# ESPREMOTE.net
KiCad netlist of a schematic drawn in EAGLE
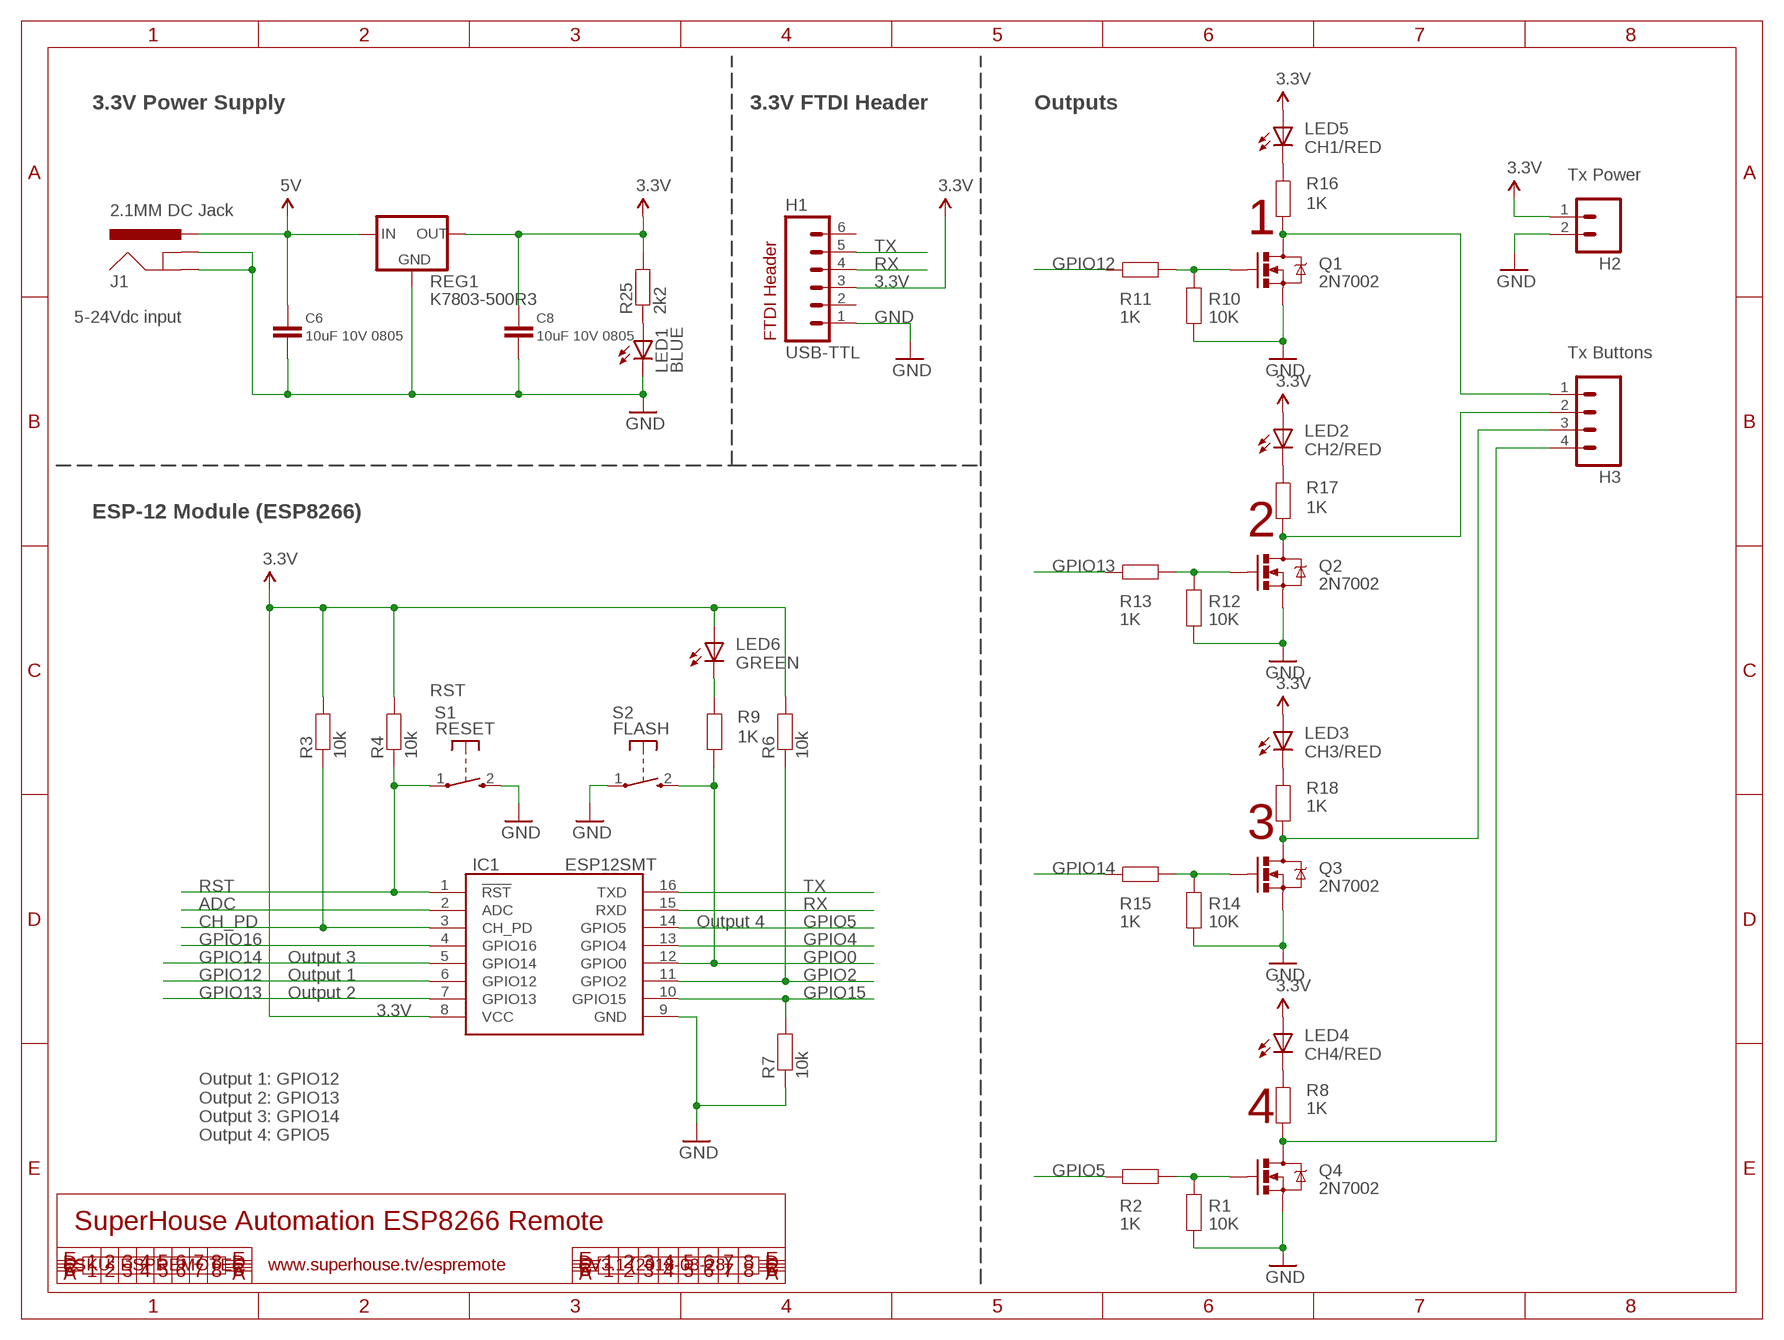
[diagram p0: schematic, sheet 1]

(export (version "E")
  (design (tool "Eeschema 10.0.6"))
  (components
    (comp (ref "C6")
      (value "10uF 10V 0805")
      (footprint "eagle-import:C0805")
      (libsource (lib "eagle-import") (part "C-EUC0805"))
    )
    (comp (ref "C8")
      (value "10uF 10V 0805")
      (footprint "eagle-import:C0805")
      (libsource (lib "eagle-import") (part "C-EUC0805"))
    )
    (comp (ref "H1")
      (value "USB-TTL")
      (footprint "eagle-import:1X06")
      (libsource (lib "eagle-import") (part "M06SIP"))
    )
    (comp (ref "H2")
      (value "M02PTH")
      (footprint "eagle-import:1X02")
      (libsource (lib "eagle-import") (part "M02PTH"))
    )
    (comp (ref "H3")
      (value "M04PTH")
      (footprint "eagle-import:1X04")
      (libsource (lib "eagle-import") (part "M04PTH"))
    )
    (comp (ref "IC1")
      (value "ESP12SMT")
      (footprint "eagle-import:ESP12")
      (libsource (lib "eagle-import") (part "ESP12SMT"))
    )
    (comp (ref "J1")
      (value "2.1MM DC Jack")
      (footprint "eagle-import:POWER_JACK_PTH_SLOTS")
      (libsource (lib "eagle-import") (part "POWER_JACKPTH_SLOTS"))
    )
    (comp (ref "LED1")
      (value "BLUE")
      (footprint "eagle-import:LED-0603")
      (libsource (lib "eagle-import") (part "LED0603"))
    )
    (comp (ref "LED2")
      (value "CH2/RED")
      (footprint "eagle-import:LED-0603")
      (libsource (lib "eagle-import") (part "freetronics-master-v1_LED0603"))
    )
    (comp (ref "LED3")
      (value "CH3/RED")
      (footprint "eagle-import:LED-0603")
      (libsource (lib "eagle-import") (part "freetronics-master-v1_LED0603"))
    )
    (comp (ref "LED4")
      (value "CH4/RED")
      (footprint "eagle-import:LED-0603")
      (libsource (lib "eagle-import") (part "freetronics-master-v1_LED0603"))
    )
    (comp (ref "LED5")
      (value "CH1/RED")
      (footprint "eagle-import:LED-0603")
      (libsource (lib "eagle-import") (part "freetronics-master-v1_LED0603"))
    )
    (comp (ref "LED6")
      (value "GREEN")
      (footprint "eagle-import:LED-0603")
      (libsource (lib "eagle-import") (part "freetronics-master-v1_LED0603"))
    )
    (comp (ref "Q1")
      (value "2N7002")
      (footprint "eagle-import:SOT23-3")
      (libsource (lib "eagle-import") (part "MOSFET-NCHANNELSMD"))
    )
    (comp (ref "Q2")
      (value "2N7002")
      (footprint "eagle-import:SOT23-3")
      (libsource (lib "eagle-import") (part "MOSFET-NCHANNELSMD"))
    )
    (comp (ref "Q3")
      (value "2N7002")
      (footprint "eagle-import:SOT23-3")
      (libsource (lib "eagle-import") (part "MOSFET-NCHANNELSMD"))
    )
    (comp (ref "Q4")
      (value "2N7002")
      (footprint "eagle-import:SOT23-3")
      (libsource (lib "eagle-import") (part "MOSFET-NCHANNELSMD"))
    )
    (comp (ref "R1")
      (value "10K")
      (footprint "eagle-import:0603")
      (libsource (lib "eagle-import") (part "freetronics-master-v1_RESISTOR0603"))
    )
    (comp (ref "R2")
      (value "1K")
      (footprint "eagle-import:0603")
      (libsource (lib "eagle-import") (part "freetronics-master-v1_RESISTOR0603"))
    )
    (comp (ref "R3")
      (value "10k")
      (footprint "eagle-import:0603")
      (libsource (lib "eagle-import") (part "RESISTOR0603"))
    )
    (comp (ref "R4")
      (value "10k")
      (footprint "eagle-import:0603")
      (libsource (lib "eagle-import") (part "RESISTOR0603"))
    )
    (comp (ref "R6")
      (value "10k")
      (footprint "eagle-import:0603")
      (libsource (lib "eagle-import") (part "RESISTOR0603"))
    )
    (comp (ref "R7")
      (value "10k")
      (footprint "eagle-import:0603")
      (libsource (lib "eagle-import") (part "RESISTOR0603"))
    )
    (comp (ref "R8")
      (value "1K")
      (footprint "eagle-import:0603")
      (libsource (lib "eagle-import") (part "freetronics-master-v1_RESISTOR0603"))
    )
    (comp (ref "R9")
      (value "1K")
      (footprint "eagle-import:0603")
      (libsource (lib "eagle-import") (part "freetronics-master-v1_RESISTOR0603"))
    )
    (comp (ref "R10")
      (value "10K")
      (footprint "eagle-import:0603")
      (libsource (lib "eagle-import") (part "freetronics-master-v1_RESISTOR0603"))
    )
    (comp (ref "R11")
      (value "1K")
      (footprint "eagle-import:0603")
      (libsource (lib "eagle-import") (part "freetronics-master-v1_RESISTOR0603"))
    )
    (comp (ref "R12")
      (value "10K")
      (footprint "eagle-import:0603")
      (libsource (lib "eagle-import") (part "freetronics-master-v1_RESISTOR0603"))
    )
    (comp (ref "R13")
      (value "1K")
      (footprint "eagle-import:0603")
      (libsource (lib "eagle-import") (part "freetronics-master-v1_RESISTOR0603"))
    )
    (comp (ref "R14")
      (value "10K")
      (footprint "eagle-import:0603")
      (libsource (lib "eagle-import") (part "freetronics-master-v1_RESISTOR0603"))
    )
    (comp (ref "R15")
      (value "1K")
      (footprint "eagle-import:0603")
      (libsource (lib "eagle-import") (part "freetronics-master-v1_RESISTOR0603"))
    )
    (comp (ref "R16")
      (value "1K")
      (footprint "eagle-import:0603")
      (libsource (lib "eagle-import") (part "freetronics-master-v1_RESISTOR0603"))
    )
    (comp (ref "R17")
      (value "1K")
      (footprint "eagle-import:0603")
      (libsource (lib "eagle-import") (part "freetronics-master-v1_RESISTOR0603"))
    )
    (comp (ref "R18")
      (value "1K")
      (footprint "eagle-import:0603")
      (libsource (lib "eagle-import") (part "freetronics-master-v1_RESISTOR0603"))
    )
    (comp (ref "R25")
      (value "2k2")
      (footprint "eagle-import:0603")
      (libsource (lib "eagle-import") (part "RESISTOR0603"))
    )
    (comp (ref "REG1")
      (value "K7803-500R3")
      (footprint "eagle-import:K78XX-500R3")
      (libsource (lib "eagle-import") (part "K78XX-500R3"))
    )
    (comp (ref "S1")
      (value "RESET")
      (footprint "eagle-import:TACTILE_SWITCH_SMD_2PIN_TINY")
      (libsource (lib "eagle-import") (part "TAC_SWITCH_2PINSMT"))
    )
    (comp (ref "S2")
      (value "FLASH")
      (footprint "eagle-import:TACTILE_SWITCH_SMD_2PIN_TINY")
      (libsource (lib "eagle-import") (part "TAC_SWITCH_2PINSMT"))
    )
  )
  (nets
    (net (code "1") (name "/ADC") (class "Default")
      (node (ref "IC1") (pin "2") (pinfunction "ADC_2") (pintype "input"))
    )
    (net (code "2") (name "/CH_PD") (class "Default")
      (node (ref "IC1") (pin "3") (pinfunction "CH_PD_3") (pintype "input"))
      (node (ref "R3") (pin "1") (pinfunction "1_1") (pintype "passive"))
    )
    (net (code "3") (name "/GPIO0") (class "Default")
      (node (ref "IC1") (pin "12") (pinfunction "GPIO0_12") (pintype "bidirectional"))
      (node (ref "R9") (pin "2") (pinfunction "2_2") (pintype "passive"))
      (node (ref "S2") (pin "2") (pinfunction "S_2") (pintype "passive"))
    )
    (net (code "4") (name "/GPIO2") (class "Default")
      (node (ref "IC1") (pin "11") (pinfunction "GPIO2_11") (pintype "bidirectional"))
      (node (ref "R6") (pin "1") (pinfunction "1_1") (pintype "passive"))
    )
    (net (code "5") (name "/GPIO4") (class "Default")
      (node (ref "IC1") (pin "13") (pinfunction "GPIO4_13") (pintype "bidirectional"))
    )
    (net (code "6") (name "/GPIO5") (class "Default")
      (node (ref "IC1") (pin "14") (pinfunction "GPIO5_14") (pintype "bidirectional"))
      (node (ref "R2") (pin "2") (pinfunction "2_2") (pintype "passive"))
    )
    (net (code "7") (name "/GPIO12") (class "Default")
      (node (ref "IC1") (pin "6") (pinfunction "GPIO12_6") (pintype "bidirectional"))
      (node (ref "R11") (pin "2") (pinfunction "2_2") (pintype "passive"))
    )
    (net (code "8") (name "/GPIO13") (class "Default")
      (node (ref "IC1") (pin "7") (pinfunction "GPIO13_7") (pintype "bidirectional"))
      (node (ref "R13") (pin "2") (pinfunction "2_2") (pintype "passive"))
    )
    (net (code "9") (name "/GPIO14") (class "Default")
      (node (ref "IC1") (pin "5") (pinfunction "GPIO14_5") (pintype "bidirectional"))
      (node (ref "R15") (pin "2") (pinfunction "2_2") (pintype "passive"))
    )
    (net (code "10") (name "/GPIO15") (class "Default")
      (node (ref "IC1") (pin "10") (pinfunction "GPIO15_10") (pintype "bidirectional"))
      (node (ref "R7") (pin "2") (pinfunction "2_2") (pintype "passive"))
    )
    (net (code "11") (name "/GPIO16") (class "Default")
      (node (ref "IC1") (pin "4") (pinfunction "GPIO16_4") (pintype "bidirectional"))
    )
    (net (code "12") (name "/RST") (class "Default")
      (node (ref "IC1") (pin "1") (pinfunction "~{RST}_1") (pintype "bidirectional"))
      (node (ref "R4") (pin "1") (pinfunction "1_1") (pintype "passive"))
      (node (ref "S1") (pin "1") (pinfunction "P_1") (pintype "passive"))
    )
    (net (code "13") (name "/RX") (class "Default")
      (node (ref "H1") (pin "4") (pinfunction "4_4") (pintype "passive"))
      (node (ref "IC1") (pin "15") (pinfunction "RXD_15") (pintype "input"))
    )
    (net (code "14") (name "/TX") (class "Default")
      (node (ref "H1") (pin "5") (pinfunction "5_5") (pintype "passive"))
      (node (ref "IC1") (pin "16") (pinfunction "TXD_16") (pintype "output"))
    )
    (net (code "15") (name "3.3V") (class "Default")
      (node (ref "C8") (pin "1") (pinfunction "1_1") (pintype "passive"))
      (node (ref "H1") (pin "3") (pinfunction "3_3") (pintype "passive"))
      (node (ref "H2") (pin "1") (pinfunction "1_1") (pintype "passive"))
      (node (ref "IC1") (pin "8") (pinfunction "VCC_8") (pintype "power_in"))
      (node (ref "LED2") (pin "A") (pinfunction "A_A") (pintype "passive"))
      (node (ref "LED3") (pin "A") (pinfunction "A_A") (pintype "passive"))
      (node (ref "LED4") (pin "A") (pinfunction "A_A") (pintype "passive"))
      (node (ref "LED5") (pin "A") (pinfunction "A_A") (pintype "passive"))
      (node (ref "LED6") (pin "A") (pinfunction "A_A") (pintype "passive"))
      (node (ref "R25") (pin "2") (pinfunction "2_2") (pintype "passive"))
      (node (ref "R3") (pin "2") (pinfunction "2_2") (pintype "passive"))
      (node (ref "R4") (pin "2") (pinfunction "2_2") (pintype "passive"))
      (node (ref "R6") (pin "2") (pinfunction "2_2") (pintype "passive"))
      (node (ref "REG1") (pin "3") (pinfunction "OUT_3") (pintype "output"))
    )
    (net (code "16") (name "5V") (class "Default")
      (node (ref "C6") (pin "1") (pinfunction "1_1") (pintype "passive"))
      (node (ref "J1") (pin "PWR") (pinfunction "PWR_PWR") (pintype "bidirectional"))
      (node (ref "REG1") (pin "1") (pinfunction "IN_1") (pintype "input"))
    )
    (net (code "17") (name "GND") (class "Default")
      (node (ref "C6") (pin "2") (pinfunction "2_2") (pintype "passive"))
      (node (ref "C8") (pin "2") (pinfunction "2_2") (pintype "passive"))
      (node (ref "H1") (pin "1") (pinfunction "1_1") (pintype "passive"))
      (node (ref "H2") (pin "2") (pinfunction "2_2") (pintype "passive"))
      (node (ref "IC1") (pin "9") (pinfunction "GND_9") (pintype "power_in"))
      (node (ref "J1") (pin "GND") (pinfunction "GND_GND") (pintype "bidirectional"))
      (node (ref "J1") (pin "GNDBREAK") (pinfunction "GNDBREAK_GNDBREAK") (pintype "bidirectional"))
      (node (ref "LED1") (pin "C") (pinfunction "C_C") (pintype "passive"))
      (node (ref "Q1") (pin "2") (pinfunction "S_2") (pintype "passive"))
      (node (ref "Q2") (pin "2") (pinfunction "S_2") (pintype "passive"))
      (node (ref "Q3") (pin "2") (pinfunction "S_2") (pintype "passive"))
      (node (ref "Q4") (pin "2") (pinfunction "S_2") (pintype "passive"))
      (node (ref "R1") (pin "1") (pinfunction "1_1") (pintype "passive"))
      (node (ref "R10") (pin "1") (pinfunction "1_1") (pintype "passive"))
      (node (ref "R12") (pin "1") (pinfunction "1_1") (pintype "passive"))
      (node (ref "R14") (pin "1") (pinfunction "1_1") (pintype "passive"))
      (node (ref "R7") (pin "1") (pinfunction "1_1") (pintype "passive"))
      (node (ref "REG1") (pin "2") (pinfunction "GND_2") (pintype "input"))
      (node (ref "S1") (pin "2") (pinfunction "S_2") (pintype "passive"))
      (node (ref "S2") (pin "1") (pinfunction "P_1") (pintype "passive"))
    )
    (net (code "18") (name "Net-(LED1-PadA)") (class "Default")
      (node (ref "LED1") (pin "A") (pinfunction "A_A") (pintype "passive"))
      (node (ref "R25") (pin "1") (pinfunction "1_1") (pintype "passive"))
    )
    (net (code "19") (name "Net-(LED2-PadC)") (class "Default")
      (node (ref "LED2") (pin "C") (pinfunction "C_C") (pintype "passive"))
      (node (ref "R17") (pin "1") (pinfunction "1_1") (pintype "passive"))
    )
    (net (code "20") (name "Net-(LED3-PadC)") (class "Default")
      (node (ref "LED3") (pin "C") (pinfunction "C_C") (pintype "passive"))
      (node (ref "R18") (pin "1") (pinfunction "1_1") (pintype "passive"))
    )
    (net (code "21") (name "Net-(LED4-PadC)") (class "Default")
      (node (ref "LED4") (pin "C") (pinfunction "C_C") (pintype "passive"))
      (node (ref "R8") (pin "1") (pinfunction "1_1") (pintype "passive"))
    )
    (net (code "22") (name "Net-(LED5-PadC)") (class "Default")
      (node (ref "LED5") (pin "C") (pinfunction "C_C") (pintype "passive"))
      (node (ref "R16") (pin "1") (pinfunction "1_1") (pintype "passive"))
    )
    (net (code "23") (name "Net-(LED6-PadC)") (class "Default")
      (node (ref "LED6") (pin "C") (pinfunction "C_C") (pintype "passive"))
      (node (ref "R9") (pin "1") (pinfunction "1_1") (pintype "passive"))
    )
    (net (code "24") (name "Net-(Q1-D)") (class "Default")
      (node (ref "H3") (pin "1") (pinfunction "1_1") (pintype "passive"))
      (node (ref "Q1") (pin "3") (pinfunction "D_3") (pintype "passive"))
      (node (ref "R16") (pin "2") (pinfunction "2_2") (pintype "passive"))
    )
    (net (code "25") (name "Net-(Q1-G)") (class "Default")
      (node (ref "Q1") (pin "1") (pinfunction "G_1") (pintype "passive"))
      (node (ref "R10") (pin "2") (pinfunction "2_2") (pintype "passive"))
      (node (ref "R11") (pin "1") (pinfunction "1_1") (pintype "passive"))
    )
    (net (code "26") (name "Net-(Q2-D)") (class "Default")
      (node (ref "H3") (pin "2") (pinfunction "2_2") (pintype "passive"))
      (node (ref "Q2") (pin "3") (pinfunction "D_3") (pintype "passive"))
      (node (ref "R17") (pin "2") (pinfunction "2_2") (pintype "passive"))
    )
    (net (code "27") (name "Net-(Q2-G)") (class "Default")
      (node (ref "Q2") (pin "1") (pinfunction "G_1") (pintype "passive"))
      (node (ref "R12") (pin "2") (pinfunction "2_2") (pintype "passive"))
      (node (ref "R13") (pin "1") (pinfunction "1_1") (pintype "passive"))
    )
    (net (code "28") (name "Net-(Q3-D)") (class "Default")
      (node (ref "H3") (pin "3") (pinfunction "3_3") (pintype "passive"))
      (node (ref "Q3") (pin "3") (pinfunction "D_3") (pintype "passive"))
      (node (ref "R18") (pin "2") (pinfunction "2_2") (pintype "passive"))
    )
    (net (code "29") (name "Net-(Q3-G)") (class "Default")
      (node (ref "Q3") (pin "1") (pinfunction "G_1") (pintype "passive"))
      (node (ref "R14") (pin "2") (pinfunction "2_2") (pintype "passive"))
      (node (ref "R15") (pin "1") (pinfunction "1_1") (pintype "passive"))
    )
    (net (code "30") (name "Net-(Q4-D)") (class "Default")
      (node (ref "H3") (pin "4") (pinfunction "4_4") (pintype "passive"))
      (node (ref "Q4") (pin "3") (pinfunction "D_3") (pintype "passive"))
      (node (ref "R8") (pin "2") (pinfunction "2_2") (pintype "passive"))
    )
    (net (code "31") (name "Net-(Q4-G)") (class "Default")
      (node (ref "Q4") (pin "1") (pinfunction "G_1") (pintype "passive"))
      (node (ref "R1") (pin "2") (pinfunction "2_2") (pintype "passive"))
      (node (ref "R2") (pin "1") (pinfunction "1_1") (pintype "passive"))
    )
    (net (code "32") (name "unconnected-(H1-Pad2)") (class "Default")
      (node (ref "H1") (pin "2") (pinfunction "2_2") (pintype "passive"))
    )
    (net (code "33") (name "unconnected-(H1-Pad6)") (class "Default")
      (node (ref "H1") (pin "6") (pinfunction "6_6") (pintype "passive"))
    )
  )
)
